# Herm_s_Phi_-_Carte_BBB_v2.net
KiCad netlist of a schematic drawn in EAGLE
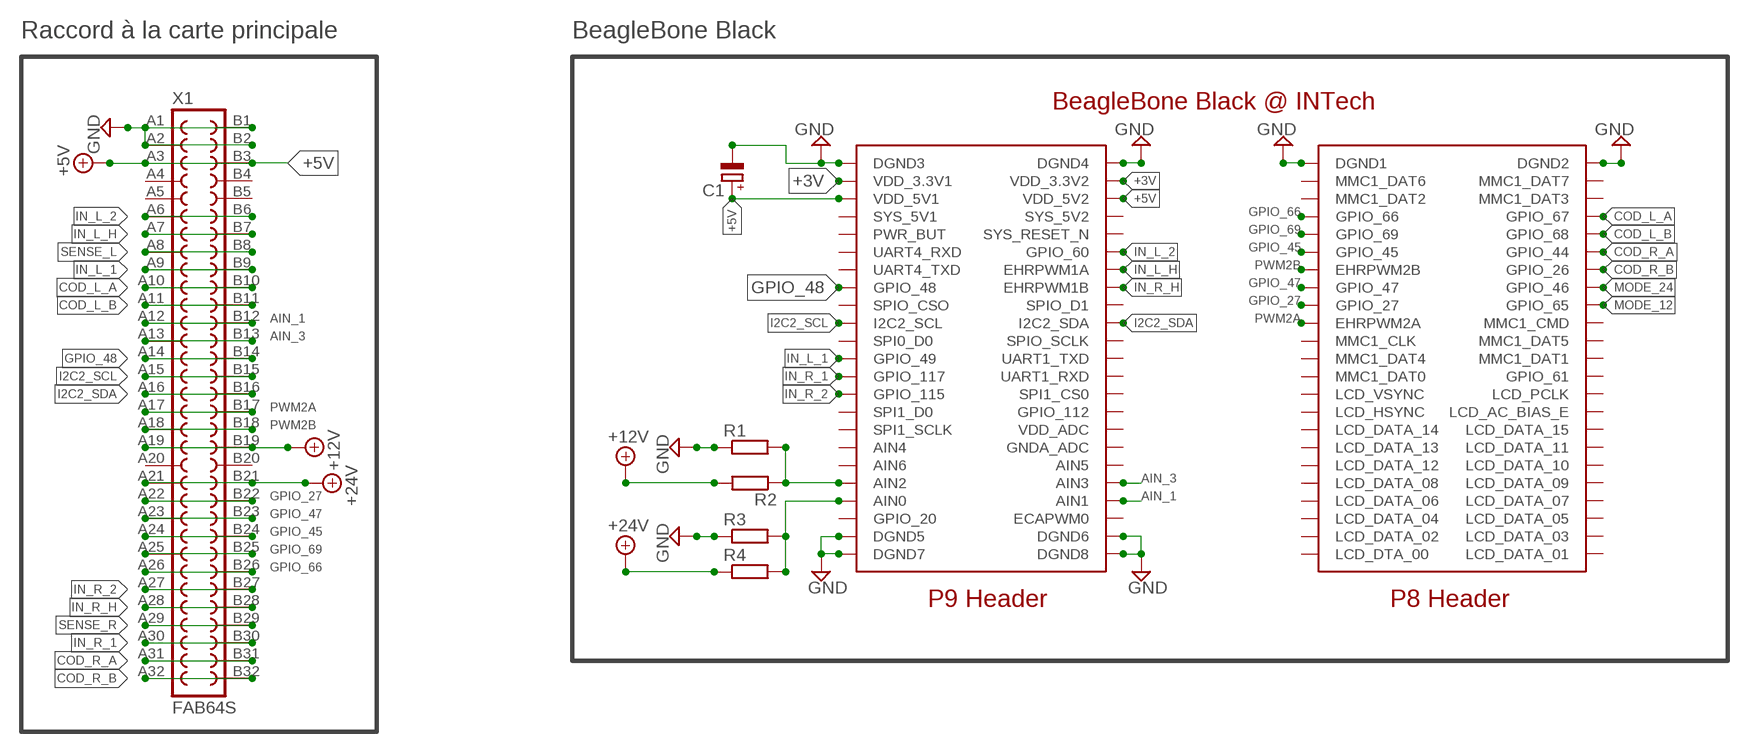
[diagram p0: schematic, sheet 1]

(export (version "E")
  (design (tool "Eeschema 10.0.6"))
  (components
    (comp (ref "C1")
      (value "CPOL-EUE2.5-5")
      (footprint "eagle-import:E2,5-5")
      (libsource (lib "eagle-import") (part "CPOL-EUE2.5-5"))
    )
    (comp (ref "R1")
      (value "R-EU_0204/7")
      (footprint "eagle-import:0204_7")
      (libsource (lib "eagle-import") (part "R-EU_0204/7"))
    )
    (comp (ref "R2")
      (value "R-EU_0204/7")
      (footprint "eagle-import:0204_7")
      (libsource (lib "eagle-import") (part "R-EU_0204/7"))
    )
    (comp (ref "R3")
      (value "R-EU_0204/7")
      (footprint "eagle-import:0204_7")
      (libsource (lib "eagle-import") (part "R-EU_0204/7"))
    )
    (comp (ref "R4")
      (value "R-EU_0204/7")
      (footprint "eagle-import:0204_7")
      (libsource (lib "eagle-import") (part "R-EU_0204/7"))
    )
    (comp (ref "U$1")
      (value "BBB")
      (footprint "eagle-import:BBB")
      (libsource (lib "eagle-import") (part "BBB"))
    )
    (comp (ref "X1")
      (value "FAB64S")
      (footprint "eagle-import:FAB64S")
      (libsource (lib "eagle-import") (part "FAB64S"))
    )
  )
  (nets
    (net (code "1") (name "+3V") (class "Default")
      (node (ref "U$1") (pin "VDD_3.3V1") (pinfunction "VDD_3.3V1_VDD_3.3V1") (pintype "bidirectional"))
      (node (ref "U$1") (pin "VDD_3.3V2") (pinfunction "VDD_3.3V2_VDD_3.3V2") (pintype "bidirectional"))
    )
    (net (code "2") (name "+5V") (class "Default")
      (node (ref "C1") (pin "+") (pinfunction "+_+") (pintype "passive"))
      (node (ref "U$1") (pin "VDD_5V1") (pinfunction "VDD_5V1_VDD_5V1") (pintype "bidirectional"))
      (node (ref "U$1") (pin "VDD_5V2") (pinfunction "VDD_5V2_VDD_5V2") (pintype "bidirectional"))
      (node (ref "X1") (pin "A3") (pinfunction "A3_A3") (pintype "passive"))
      (node (ref "X1") (pin "B3") (pinfunction "B3_B3") (pintype "passive"))
    )
    (net (code "3") (name "+12V") (class "Default")
      (node (ref "R2") (pin "2") (pinfunction "2_2") (pintype "passive"))
      (node (ref "X1") (pin "A19") (pinfunction "A19_A19") (pintype "passive"))
      (node (ref "X1") (pin "B19") (pinfunction "B19_B19") (pintype "passive"))
    )
    (net (code "4") (name "+24V") (class "Default")
      (node (ref "R4") (pin "1") (pinfunction "1_1") (pintype "passive"))
      (node (ref "X1") (pin "A21") (pinfunction "A21_A21") (pintype "passive"))
      (node (ref "X1") (pin "B21") (pinfunction "B21_B21") (pintype "passive"))
    )
    (net (code "5") (name "/AIN_1") (class "Default")
      (node (ref "U$1") (pin "AIN1") (pinfunction "AIN1_AIN1") (pintype "bidirectional"))
      (node (ref "X1") (pin "A12") (pinfunction "A12_A12") (pintype "passive"))
      (node (ref "X1") (pin "B12") (pinfunction "B12_B12") (pintype "passive"))
    )
    (net (code "6") (name "/AIN_3") (class "Default")
      (node (ref "U$1") (pin "AIN3") (pinfunction "AIN3_AIN3") (pintype "bidirectional"))
      (node (ref "X1") (pin "A13") (pinfunction "A13_A13") (pintype "passive"))
      (node (ref "X1") (pin "B13") (pinfunction "B13_B13") (pintype "passive"))
    )
    (net (code "7") (name "/GPIO_27") (class "Default")
      (node (ref "U$1") (pin "GPIO_27") (pinfunction "GPIO_27_GPIO_27") (pintype "bidirectional"))
      (node (ref "X1") (pin "A22") (pinfunction "A22_A22") (pintype "passive"))
      (node (ref "X1") (pin "B22") (pinfunction "B22_B22") (pintype "passive"))
    )
    (net (code "8") (name "/GPIO_45") (class "Default")
      (node (ref "U$1") (pin "GPIO_45") (pinfunction "GPIO_45_GPIO_45") (pintype "bidirectional"))
      (node (ref "X1") (pin "A24") (pinfunction "A24_A24") (pintype "passive"))
      (node (ref "X1") (pin "B24") (pinfunction "B24_B24") (pintype "passive"))
    )
    (net (code "9") (name "/GPIO_47") (class "Default")
      (node (ref "U$1") (pin "GPIO_47") (pinfunction "GPIO_47_GPIO_47") (pintype "bidirectional"))
      (node (ref "X1") (pin "A23") (pinfunction "A23_A23") (pintype "passive"))
      (node (ref "X1") (pin "B23") (pinfunction "B23_B23") (pintype "passive"))
    )
    (net (code "10") (name "/GPIO_66") (class "Default")
      (node (ref "U$1") (pin "GPIO_66") (pinfunction "GPIO_66_GPIO_66") (pintype "bidirectional"))
      (node (ref "X1") (pin "A26") (pinfunction "A26_A26") (pintype "passive"))
      (node (ref "X1") (pin "B26") (pinfunction "B26_B26") (pintype "passive"))
    )
    (net (code "11") (name "/GPIO_69") (class "Default")
      (node (ref "U$1") (pin "GPIO_69") (pinfunction "GPIO_69_GPIO_69") (pintype "bidirectional"))
      (node (ref "X1") (pin "A25") (pinfunction "A25_A25") (pintype "passive"))
      (node (ref "X1") (pin "B25") (pinfunction "B25_B25") (pintype "passive"))
    )
    (net (code "12") (name "/PWM2A") (class "Default")
      (node (ref "U$1") (pin "EHRPWM2A") (pinfunction "EHRPWM2A_EHRPWM2A") (pintype "bidirectional"))
      (node (ref "X1") (pin "A17") (pinfunction "A17_A17") (pintype "passive"))
      (node (ref "X1") (pin "B17") (pinfunction "B17_B17") (pintype "passive"))
    )
    (net (code "13") (name "/PWM2B") (class "Default")
      (node (ref "U$1") (pin "EHRPWMB2") (pinfunction "EHRPWM2B_EHRPWMB2") (pintype "bidirectional"))
      (node (ref "X1") (pin "A18") (pinfunction "A18_A18") (pintype "passive"))
      (node (ref "X1") (pin "B18") (pinfunction "B18_B18") (pintype "passive"))
    )
    (net (code "14") (name "COD_L_A") (class "Default")
      (node (ref "U$1") (pin "GPIO_67") (pinfunction "GPIO_67_GPIO_67") (pintype "bidirectional"))
      (node (ref "X1") (pin "A10") (pinfunction "A10_A10") (pintype "passive"))
      (node (ref "X1") (pin "B10") (pinfunction "B10_B10") (pintype "passive"))
    )
    (net (code "15") (name "COD_L_B") (class "Default")
      (node (ref "U$1") (pin "GPIO_68") (pinfunction "GPIO_68_GPIO_68") (pintype "bidirectional"))
      (node (ref "X1") (pin "A11") (pinfunction "A11_A11") (pintype "passive"))
      (node (ref "X1") (pin "B11") (pinfunction "B11_B11") (pintype "passive"))
    )
    (net (code "16") (name "COD_R_A") (class "Default")
      (node (ref "U$1") (pin "GPIO_44") (pinfunction "GPIO_44_GPIO_44") (pintype "bidirectional"))
      (node (ref "X1") (pin "A31") (pinfunction "A31_A31") (pintype "passive"))
      (node (ref "X1") (pin "B31") (pinfunction "B31_B31") (pintype "passive"))
    )
    (net (code "17") (name "COD_R_B") (class "Default")
      (node (ref "U$1") (pin "GPIO_26") (pinfunction "GPIO_26_GPIO_26") (pintype "bidirectional"))
      (node (ref "X1") (pin "A32") (pinfunction "A32_A32") (pintype "passive"))
      (node (ref "X1") (pin "B32") (pinfunction "B32_B32") (pintype "passive"))
    )
    (net (code "18") (name "GND") (class "Default")
      (node (ref "C1") (pin "-") (pinfunction "-_-") (pintype "passive"))
      (node (ref "R1") (pin "1") (pinfunction "1_1") (pintype "passive"))
      (node (ref "R3") (pin "1") (pinfunction "1_1") (pintype "passive"))
      (node (ref "U$1") (pin "DGND1") (pinfunction "DGND1_DGND1") (pintype "bidirectional"))
      (node (ref "U$1") (pin "DGND2") (pinfunction "DGND2_DGND2") (pintype "bidirectional"))
      (node (ref "U$1") (pin "DGND3") (pinfunction "DGND3_DGND3") (pintype "bidirectional"))
      (node (ref "U$1") (pin "DGND4") (pinfunction "DGND4_DGND4") (pintype "bidirectional"))
      (node (ref "U$1") (pin "DGND5") (pinfunction "DGND5_DGND5") (pintype "bidirectional"))
      (node (ref "U$1") (pin "DGND6") (pinfunction "DGND6_DGND6") (pintype "bidirectional"))
      (node (ref "U$1") (pin "DGND7") (pinfunction "DGND7_DGND7") (pintype "bidirectional"))
      (node (ref "U$1") (pin "DGND8") (pinfunction "DGND8_DGND8") (pintype "bidirectional"))
      (node (ref "X1") (pin "A1") (pinfunction "A1_A1") (pintype "passive"))
      (node (ref "X1") (pin "A2") (pinfunction "A2_A2") (pintype "passive"))
      (node (ref "X1") (pin "B1") (pinfunction "B1_B1") (pintype "passive"))
      (node (ref "X1") (pin "B2") (pinfunction "B2_B2") (pintype "passive"))
    )
    (net (code "19") (name "GPIO_48") (class "Default")
      (node (ref "U$1") (pin "GPIO_48") (pinfunction "GPIO_48_GPIO_48") (pintype "bidirectional"))
      (node (ref "X1") (pin "A14") (pinfunction "A14_A14") (pintype "passive"))
      (node (ref "X1") (pin "B14") (pinfunction "B14_B14") (pintype "passive"))
    )
    (net (code "20") (name "I2C2_SCL") (class "Default")
      (node (ref "U$1") (pin "I2C2_SCL") (pinfunction "I2C2_SCL_I2C2_SCL") (pintype "bidirectional"))
      (node (ref "X1") (pin "A15") (pinfunction "A15_A15") (pintype "passive"))
      (node (ref "X1") (pin "B15") (pinfunction "B15_B15") (pintype "passive"))
    )
    (net (code "21") (name "I2C2_SDA") (class "Default")
      (node (ref "U$1") (pin "I2C_SDA") (pinfunction "I2C2_SDA_I2C_SDA") (pintype "bidirectional"))
      (node (ref "X1") (pin "A16") (pinfunction "A16_A16") (pintype "passive"))
      (node (ref "X1") (pin "B16") (pinfunction "B16_B16") (pintype "passive"))
    )
    (net (code "22") (name "IN_L_1") (class "Default")
      (node (ref "U$1") (pin "GPIO_49") (pinfunction "GPIO_49_GPIO_49") (pintype "bidirectional"))
      (node (ref "X1") (pin "A9") (pinfunction "A9_A9") (pintype "passive"))
      (node (ref "X1") (pin "B9") (pinfunction "B9_B9") (pintype "passive"))
    )
    (net (code "23") (name "IN_L_2") (class "Default")
      (node (ref "U$1") (pin "GPIO_60") (pinfunction "GPIO_60_GPIO_60") (pintype "bidirectional"))
      (node (ref "X1") (pin "A6") (pinfunction "A6_A6") (pintype "passive"))
      (node (ref "X1") (pin "B6") (pinfunction "B6_B6") (pintype "passive"))
    )
    (net (code "24") (name "IN_L_H") (class "Default")
      (node (ref "U$1") (pin "EHRPWM1A") (pinfunction "EHRPWM1A_EHRPWM1A") (pintype "bidirectional"))
      (node (ref "X1") (pin "A7") (pinfunction "A7_A7") (pintype "passive"))
      (node (ref "X1") (pin "B7") (pinfunction "B7_B7") (pintype "passive"))
    )
    (net (code "25") (name "IN_R_1") (class "Default")
      (node (ref "U$1") (pin "GPIO_117") (pinfunction "GPIO_117_GPIO_117") (pintype "bidirectional"))
      (node (ref "X1") (pin "A30") (pinfunction "A30_A30") (pintype "passive"))
      (node (ref "X1") (pin "B30") (pinfunction "B30_B30") (pintype "passive"))
    )
    (net (code "26") (name "IN_R_2") (class "Default")
      (node (ref "U$1") (pin "GPIO_115") (pinfunction "GPIO_115_GPIO_115") (pintype "bidirectional"))
      (node (ref "X1") (pin "A27") (pinfunction "A27_A27") (pintype "passive"))
      (node (ref "X1") (pin "B27") (pinfunction "B27_B27") (pintype "passive"))
    )
    (net (code "27") (name "IN_R_H") (class "Default")
      (node (ref "U$1") (pin "EHRPWM1B") (pinfunction "EHRPWM1B_EHRPWM1B") (pintype "bidirectional"))
      (node (ref "X1") (pin "A28") (pinfunction "A28_A28") (pintype "passive"))
      (node (ref "X1") (pin "B28") (pinfunction "B28_B28") (pintype "passive"))
    )
    (net (code "28") (name "MODE_12") (class "Default")
      (node (ref "U$1") (pin "GPIO_65") (pinfunction "GPIO_65_GPIO_65") (pintype "bidirectional"))
    )
    (net (code "29") (name "MODE_24") (class "Default")
      (node (ref "U$1") (pin "GPIO_46") (pinfunction "GPIO_46_GPIO_46") (pintype "bidirectional"))
    )
    (net (code "30") (name "Net-(R1-Pad2)") (class "Default")
      (node (ref "R1") (pin "2") (pinfunction "2_2") (pintype "passive"))
      (node (ref "R2") (pin "1") (pinfunction "1_1") (pintype "passive"))
      (node (ref "U$1") (pin "AIN2") (pinfunction "AIN2_AIN2") (pintype "bidirectional"))
    )
    (net (code "31") (name "Net-(R3-Pad2)") (class "Default")
      (node (ref "R3") (pin "2") (pinfunction "2_2") (pintype "passive"))
      (node (ref "R4") (pin "2") (pinfunction "2_2") (pintype "passive"))
      (node (ref "U$1") (pin "AIN0") (pinfunction "AIN0_AIN0") (pintype "bidirectional"))
    )
    (net (code "32") (name "SENSE_L") (class "Default")
      (node (ref "X1") (pin "A8") (pinfunction "A8_A8") (pintype "passive"))
      (node (ref "X1") (pin "B8") (pinfunction "B8_B8") (pintype "passive"))
    )
    (net (code "33") (name "SENSE_R") (class "Default")
      (node (ref "X1") (pin "A29") (pinfunction "A29_A29") (pintype "passive"))
      (node (ref "X1") (pin "B29") (pinfunction "B29_B29") (pintype "passive"))
    )
    (net (code "34") (name "unconnected-(U$1-GNDA_ADC-PadGND_ADC)") (class "Default")
      (node (ref "U$1") (pin "GND_ADC") (pinfunction "GNDA_ADC_GND_ADC") (pintype "bidirectional"))
    )
    (net (code "35") (name "unconnected-(U$1-LCD_AC_BIAS_E-PadLCD_AC_BIAS)") (class "Default")
      (node (ref "U$1") (pin "LCD_AC_BIAS") (pinfunction "LCD_AC_BIAS_E_LCD_AC_BIAS") (pintype "bidirectional"))
    )
    (net (code "36") (name "unconnected-(U$1-LCD_DATA_03-PadLCD_DTA_03)") (class "Default")
      (node (ref "U$1") (pin "LCD_DTA_03") (pinfunction "LCD_DATA_03_LCD_DTA_03") (pintype "bidirectional"))
    )
    (net (code "37") (name "unconnected-(U$1-LCD_DTA_00-PadLCD_DATA_0)") (class "Default")
      (node (ref "U$1") (pin "LCD_DATA_0") (pinfunction "LCD_DTA_00_LCD_DATA_0") (pintype "bidirectional"))
    )
    (net (code "38") (name "unconnected-(U$1-PadAIN4)") (class "Default")
      (node (ref "U$1") (pin "AIN4") (pinfunction "AIN4_AIN4") (pintype "bidirectional"))
    )
    (net (code "39") (name "unconnected-(U$1-PadAIN5)") (class "Default")
      (node (ref "U$1") (pin "AIN5") (pinfunction "AIN5_AIN5") (pintype "bidirectional"))
    )
    (net (code "40") (name "unconnected-(U$1-PadAIN6)") (class "Default")
      (node (ref "U$1") (pin "AIN6") (pinfunction "AIN6_AIN6") (pintype "bidirectional"))
    )
    (net (code "41") (name "unconnected-(U$1-PadECAPWM0)") (class "Default")
      (node (ref "U$1") (pin "ECAPWM0") (pinfunction "ECAPWM0_ECAPWM0") (pintype "bidirectional"))
    )
    (net (code "42") (name "unconnected-(U$1-PadGPIO_20)") (class "Default")
      (node (ref "U$1") (pin "GPIO_20") (pinfunction "GPIO_20_GPIO_20") (pintype "bidirectional"))
    )
    (net (code "43") (name "unconnected-(U$1-PadGPIO_61)") (class "Default")
      (node (ref "U$1") (pin "GPIO_61") (pinfunction "GPIO_61_GPIO_61") (pintype "bidirectional"))
    )
    (net (code "44") (name "unconnected-(U$1-PadGPIO_112)") (class "Default")
      (node (ref "U$1") (pin "GPIO_112") (pinfunction "GPIO_112_GPIO_112") (pintype "bidirectional"))
    )
    (net (code "45") (name "unconnected-(U$1-PadLCD_DATA_01)") (class "Default")
      (node (ref "U$1") (pin "LCD_DATA_01") (pinfunction "LCD_DATA_01_LCD_DATA_01") (pintype "bidirectional"))
    )
    (net (code "46") (name "unconnected-(U$1-PadLCD_DATA_02)") (class "Default")
      (node (ref "U$1") (pin "LCD_DATA_02") (pinfunction "LCD_DATA_02_LCD_DATA_02") (pintype "bidirectional"))
    )
    (net (code "47") (name "unconnected-(U$1-PadLCD_DATA_04)") (class "Default")
      (node (ref "U$1") (pin "LCD_DATA_04") (pinfunction "LCD_DATA_04_LCD_DATA_04") (pintype "bidirectional"))
    )
    (net (code "48") (name "unconnected-(U$1-PadLCD_DATA_05)") (class "Default")
      (node (ref "U$1") (pin "LCD_DATA_05") (pinfunction "LCD_DATA_05_LCD_DATA_05") (pintype "bidirectional"))
    )
    (net (code "49") (name "unconnected-(U$1-PadLCD_DATA_06)") (class "Default")
      (node (ref "U$1") (pin "LCD_DATA_06") (pinfunction "LCD_DATA_06_LCD_DATA_06") (pintype "bidirectional"))
    )
    (net (code "50") (name "unconnected-(U$1-PadLCD_DATA_07)") (class "Default")
      (node (ref "U$1") (pin "LCD_DATA_07") (pinfunction "LCD_DATA_07_LCD_DATA_07") (pintype "bidirectional"))
    )
    (net (code "51") (name "unconnected-(U$1-PadLCD_DATA_08)") (class "Default")
      (node (ref "U$1") (pin "LCD_DATA_08") (pinfunction "LCD_DATA_08_LCD_DATA_08") (pintype "bidirectional"))
    )
    (net (code "52") (name "unconnected-(U$1-PadLCD_DATA_09)") (class "Default")
      (node (ref "U$1") (pin "LCD_DATA_09") (pinfunction "LCD_DATA_09_LCD_DATA_09") (pintype "bidirectional"))
    )
    (net (code "53") (name "unconnected-(U$1-PadLCD_DATA_10)") (class "Default")
      (node (ref "U$1") (pin "LCD_DATA_10") (pinfunction "LCD_DATA_10_LCD_DATA_10") (pintype "bidirectional"))
    )
    (net (code "54") (name "unconnected-(U$1-PadLCD_DATA_11)") (class "Default")
      (node (ref "U$1") (pin "LCD_DATA_11") (pinfunction "LCD_DATA_11_LCD_DATA_11") (pintype "bidirectional"))
    )
    (net (code "55") (name "unconnected-(U$1-PadLCD_DATA_12)") (class "Default")
      (node (ref "U$1") (pin "LCD_DATA_12") (pinfunction "LCD_DATA_12_LCD_DATA_12") (pintype "bidirectional"))
    )
    (net (code "56") (name "unconnected-(U$1-PadLCD_DATA_13)") (class "Default")
      (node (ref "U$1") (pin "LCD_DATA_13") (pinfunction "LCD_DATA_13_LCD_DATA_13") (pintype "bidirectional"))
    )
    (net (code "57") (name "unconnected-(U$1-PadLCD_DATA_14)") (class "Default")
      (node (ref "U$1") (pin "LCD_DATA_14") (pinfunction "LCD_DATA_14_LCD_DATA_14") (pintype "bidirectional"))
    )
    (net (code "58") (name "unconnected-(U$1-PadLCD_DATA_15)") (class "Default")
      (node (ref "U$1") (pin "LCD_DATA_15") (pinfunction "LCD_DATA_15_LCD_DATA_15") (pintype "bidirectional"))
    )
    (net (code "59") (name "unconnected-(U$1-PadLCD_HSYNC)") (class "Default")
      (node (ref "U$1") (pin "LCD_HSYNC") (pinfunction "LCD_HSYNC_LCD_HSYNC") (pintype "bidirectional"))
    )
    (net (code "60") (name "unconnected-(U$1-PadLCD_PCLK)") (class "Default")
      (node (ref "U$1") (pin "LCD_PCLK") (pinfunction "LCD_PCLK_LCD_PCLK") (pintype "bidirectional"))
    )
    (net (code "61") (name "unconnected-(U$1-PadLCD_VSYNC)") (class "Default")
      (node (ref "U$1") (pin "LCD_VSYNC") (pinfunction "LCD_VSYNC_LCD_VSYNC") (pintype "bidirectional"))
    )
    (net (code "62") (name "unconnected-(U$1-PadMMC1_CLK)") (class "Default")
      (node (ref "U$1") (pin "MMC1_CLK") (pinfunction "MMC1_CLK_MMC1_CLK") (pintype "bidirectional"))
    )
    (net (code "63") (name "unconnected-(U$1-PadMMC1_CMD)") (class "Default")
      (node (ref "U$1") (pin "MMC1_CMD") (pinfunction "MMC1_CMD_MMC1_CMD") (pintype "bidirectional"))
    )
    (net (code "64") (name "unconnected-(U$1-PadMMC1_DAT0)") (class "Default")
      (node (ref "U$1") (pin "MMC1_DAT0") (pinfunction "MMC1_DAT0_MMC1_DAT0") (pintype "bidirectional"))
    )
    (net (code "65") (name "unconnected-(U$1-PadMMC1_DAT1)") (class "Default")
      (node (ref "U$1") (pin "MMC1_DAT1") (pinfunction "MMC1_DAT1_MMC1_DAT1") (pintype "bidirectional"))
    )
    (net (code "66") (name "unconnected-(U$1-PadMMC1_DAT2)") (class "Default")
      (node (ref "U$1") (pin "MMC1_DAT2") (pinfunction "MMC1_DAT2_MMC1_DAT2") (pintype "bidirectional"))
    )
    (net (code "67") (name "unconnected-(U$1-PadMMC1_DAT3)") (class "Default")
      (node (ref "U$1") (pin "MMC1_DAT3") (pinfunction "MMC1_DAT3_MMC1_DAT3") (pintype "bidirectional"))
    )
    (net (code "68") (name "unconnected-(U$1-PadMMC1_DAT4)") (class "Default")
      (node (ref "U$1") (pin "MMC1_DAT4") (pinfunction "MMC1_DAT4_MMC1_DAT4") (pintype "bidirectional"))
    )
    (net (code "69") (name "unconnected-(U$1-PadMMC1_DAT5)") (class "Default")
      (node (ref "U$1") (pin "MMC1_DAT5") (pinfunction "MMC1_DAT5_MMC1_DAT5") (pintype "bidirectional"))
    )
    (net (code "70") (name "unconnected-(U$1-PadMMC1_DAT6)") (class "Default")
      (node (ref "U$1") (pin "MMC1_DAT6") (pinfunction "MMC1_DAT6_MMC1_DAT6") (pintype "bidirectional"))
    )
    (net (code "71") (name "unconnected-(U$1-PadMMC1_DAT7)") (class "Default")
      (node (ref "U$1") (pin "MMC1_DAT7") (pinfunction "MMC1_DAT7_MMC1_DAT7") (pintype "bidirectional"))
    )
    (net (code "72") (name "unconnected-(U$1-PadPWR_BUT)") (class "Default")
      (node (ref "U$1") (pin "PWR_BUT") (pinfunction "PWR_BUT_PWR_BUT") (pintype "bidirectional"))
    )
    (net (code "73") (name "unconnected-(U$1-PadSPI1_SCLK)") (class "Default")
      (node (ref "U$1") (pin "SPI1_SCLK") (pinfunction "SPI1_SCLK_SPI1_SCLK") (pintype "bidirectional"))
    )
    (net (code "74") (name "unconnected-(U$1-PadSPIO_CSO)") (class "Default")
      (node (ref "U$1") (pin "SPIO_CSO") (pinfunction "SPIO_CSO_SPIO_CSO") (pintype "bidirectional"))
    )
    (net (code "75") (name "unconnected-(U$1-PadSPIO_D1)") (class "Default")
      (node (ref "U$1") (pin "SPIO_D1") (pinfunction "SPIO_D1_SPIO_D1") (pintype "bidirectional"))
    )
    (net (code "76") (name "unconnected-(U$1-PadSPIO_SCLK)") (class "Default")
      (node (ref "U$1") (pin "SPIO_SCLK") (pinfunction "SPIO_SCLK_SPIO_SCLK") (pintype "bidirectional"))
    )
    (net (code "77") (name "unconnected-(U$1-PadSYS_5V1)") (class "Default")
      (node (ref "U$1") (pin "SYS_5V1") (pinfunction "SYS_5V1_SYS_5V1") (pintype "bidirectional"))
    )
    (net (code "78") (name "unconnected-(U$1-PadSYS_5V2)") (class "Default")
      (node (ref "U$1") (pin "SYS_5V2") (pinfunction "SYS_5V2_SYS_5V2") (pintype "bidirectional"))
    )
    (net (code "79") (name "unconnected-(U$1-PadUART1_RXD)") (class "Default")
      (node (ref "U$1") (pin "UART1_RXD") (pinfunction "UART1_RXD_UART1_RXD") (pintype "bidirectional"))
    )
    (net (code "80") (name "unconnected-(U$1-PadUART1_TXD)") (class "Default")
      (node (ref "U$1") (pin "UART1_TXD") (pinfunction "UART1_TXD_UART1_TXD") (pintype "bidirectional"))
    )
    (net (code "81") (name "unconnected-(U$1-PadUART4_RXD)") (class "Default")
      (node (ref "U$1") (pin "UART4_RXD") (pinfunction "UART4_RXD_UART4_RXD") (pintype "bidirectional"))
    )
    (net (code "82") (name "unconnected-(U$1-PadUART4_TXD)") (class "Default")
      (node (ref "U$1") (pin "UART4_TXD") (pinfunction "UART4_TXD_UART4_TXD") (pintype "bidirectional"))
    )
    (net (code "83") (name "unconnected-(U$1-PadVDD_ADC)") (class "Default")
      (node (ref "U$1") (pin "VDD_ADC") (pinfunction "VDD_ADC_VDD_ADC") (pintype "bidirectional"))
    )
    (net (code "84") (name "unconnected-(U$1-SPI0_D0-PadSPI1_DO)") (class "Default")
      (node (ref "U$1") (pin "SPI1_DO") (pinfunction "SPI0_D0_SPI1_DO") (pintype "bidirectional"))
    )
    (net (code "85") (name "unconnected-(U$1-SPI1_CS0-PadSPI1_SCO)") (class "Default")
      (node (ref "U$1") (pin "SPI1_SCO") (pinfunction "SPI1_CS0_SPI1_SCO") (pintype "bidirectional"))
    )
    (net (code "86") (name "unconnected-(U$1-SPI1_D0-PadSPIO_D0)") (class "Default")
      (node (ref "U$1") (pin "SPIO_D0") (pinfunction "SPI1_D0_SPIO_D0") (pintype "bidirectional"))
    )
    (net (code "87") (name "unconnected-(U$1-SYS_RESET_N-PadSYS_RESET)") (class "Default")
      (node (ref "U$1") (pin "SYS_RESET") (pinfunction "SYS_RESET_N_SYS_RESET") (pintype "bidirectional"))
    )
    (net (code "88") (name "unconnected-(X1-PadA4)") (class "Default")
      (node (ref "X1") (pin "A4") (pinfunction "A4_A4") (pintype "passive"))
    )
    (net (code "89") (name "unconnected-(X1-PadA5)") (class "Default")
      (node (ref "X1") (pin "A5") (pinfunction "A5_A5") (pintype "passive"))
    )
    (net (code "90") (name "unconnected-(X1-PadA20)") (class "Default")
      (node (ref "X1") (pin "A20") (pinfunction "A20_A20") (pintype "passive"))
    )
    (net (code "91") (name "unconnected-(X1-PadB4)") (class "Default")
      (node (ref "X1") (pin "B4") (pinfunction "B4_B4") (pintype "passive"))
    )
    (net (code "92") (name "unconnected-(X1-PadB5)") (class "Default")
      (node (ref "X1") (pin "B5") (pinfunction "B5_B5") (pintype "passive"))
    )
    (net (code "93") (name "unconnected-(X1-PadB20)") (class "Default")
      (node (ref "X1") (pin "B20") (pinfunction "B20_B20") (pintype "passive"))
    )
  )
)
